# schematic.net
KiCad netlist of a schematic drawn in EAGLE
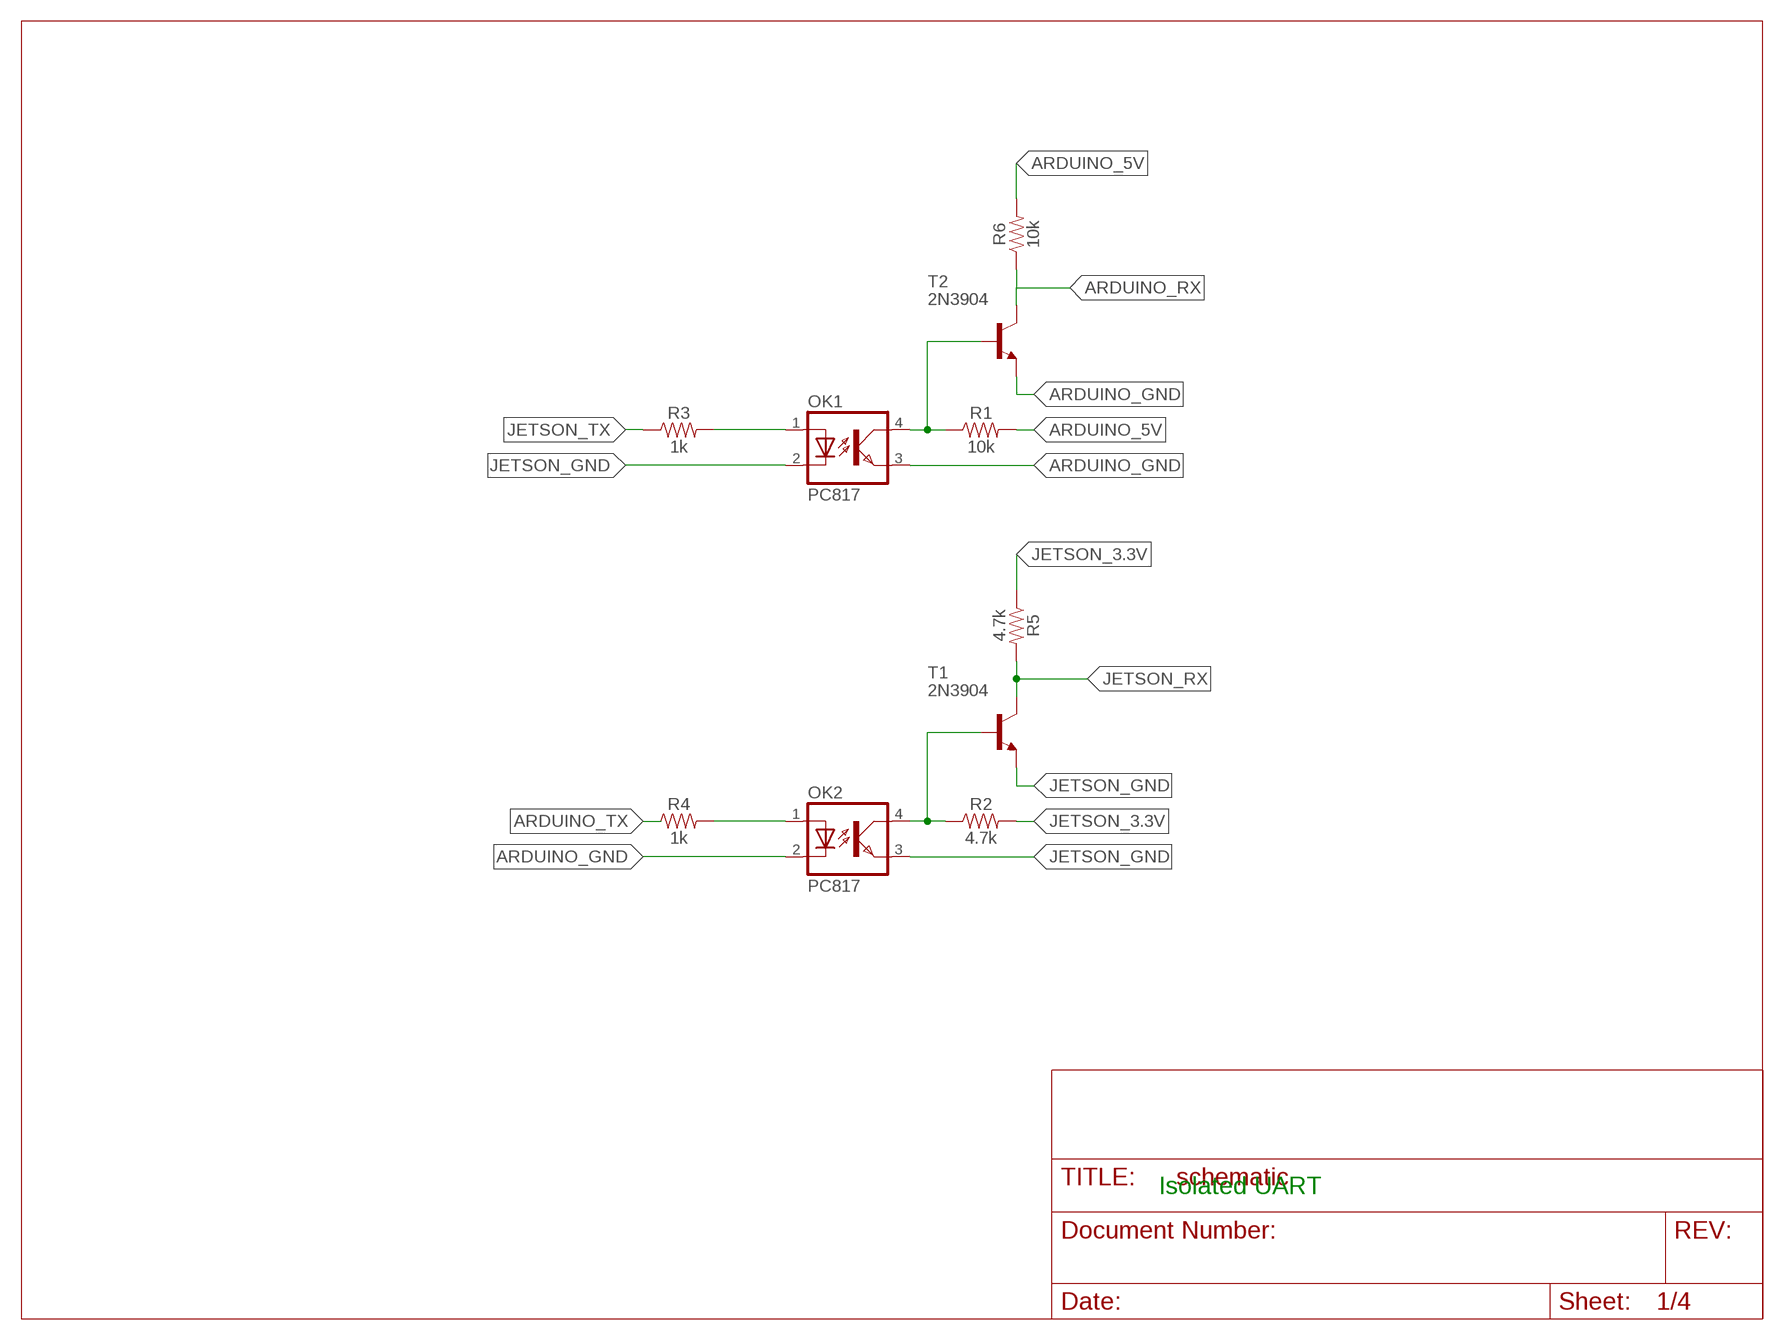
[diagram p0: schematic, sheet 1]
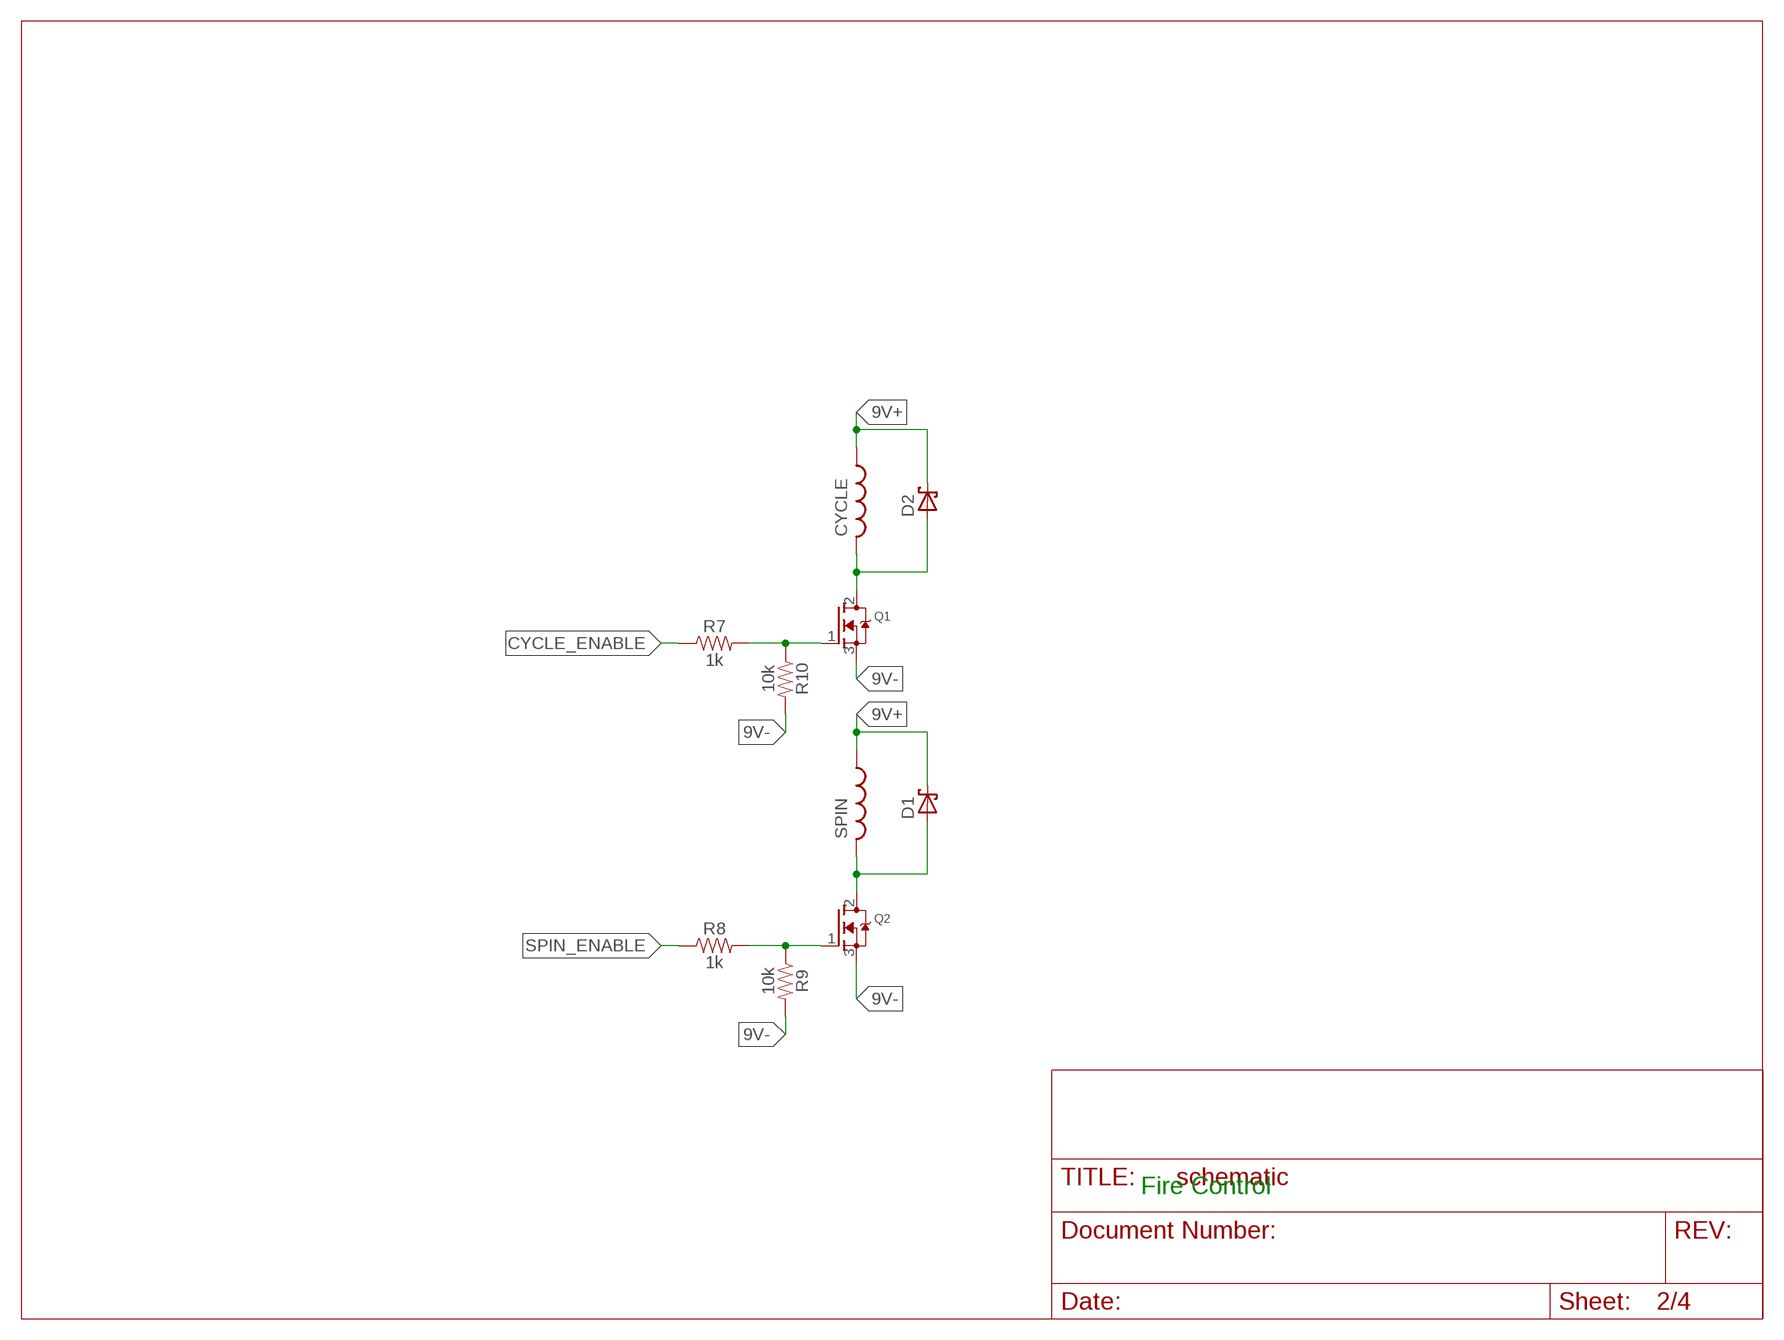
[diagram p1: schematic, sheet 2]
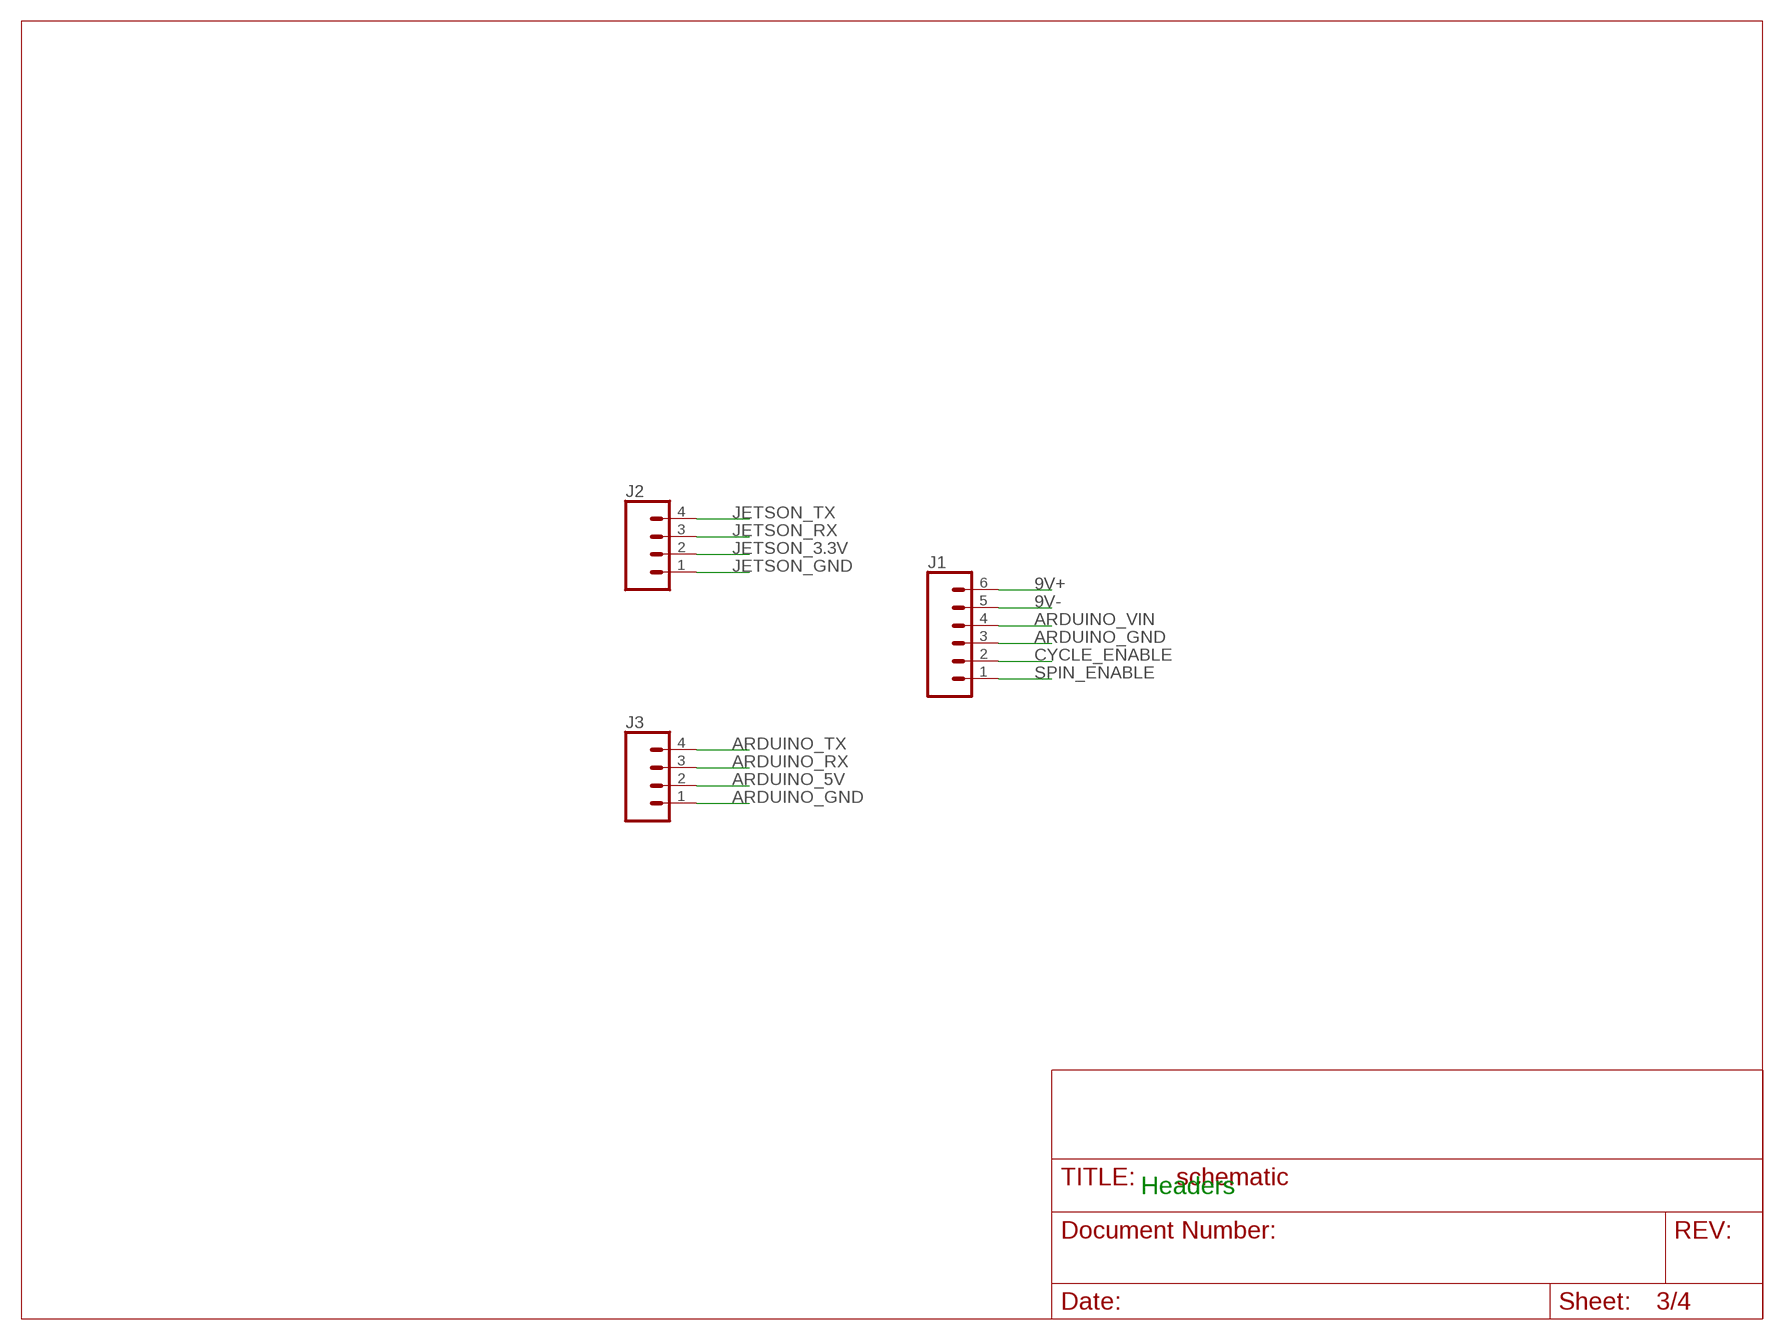
[diagram p2: schematic, sheet 3]
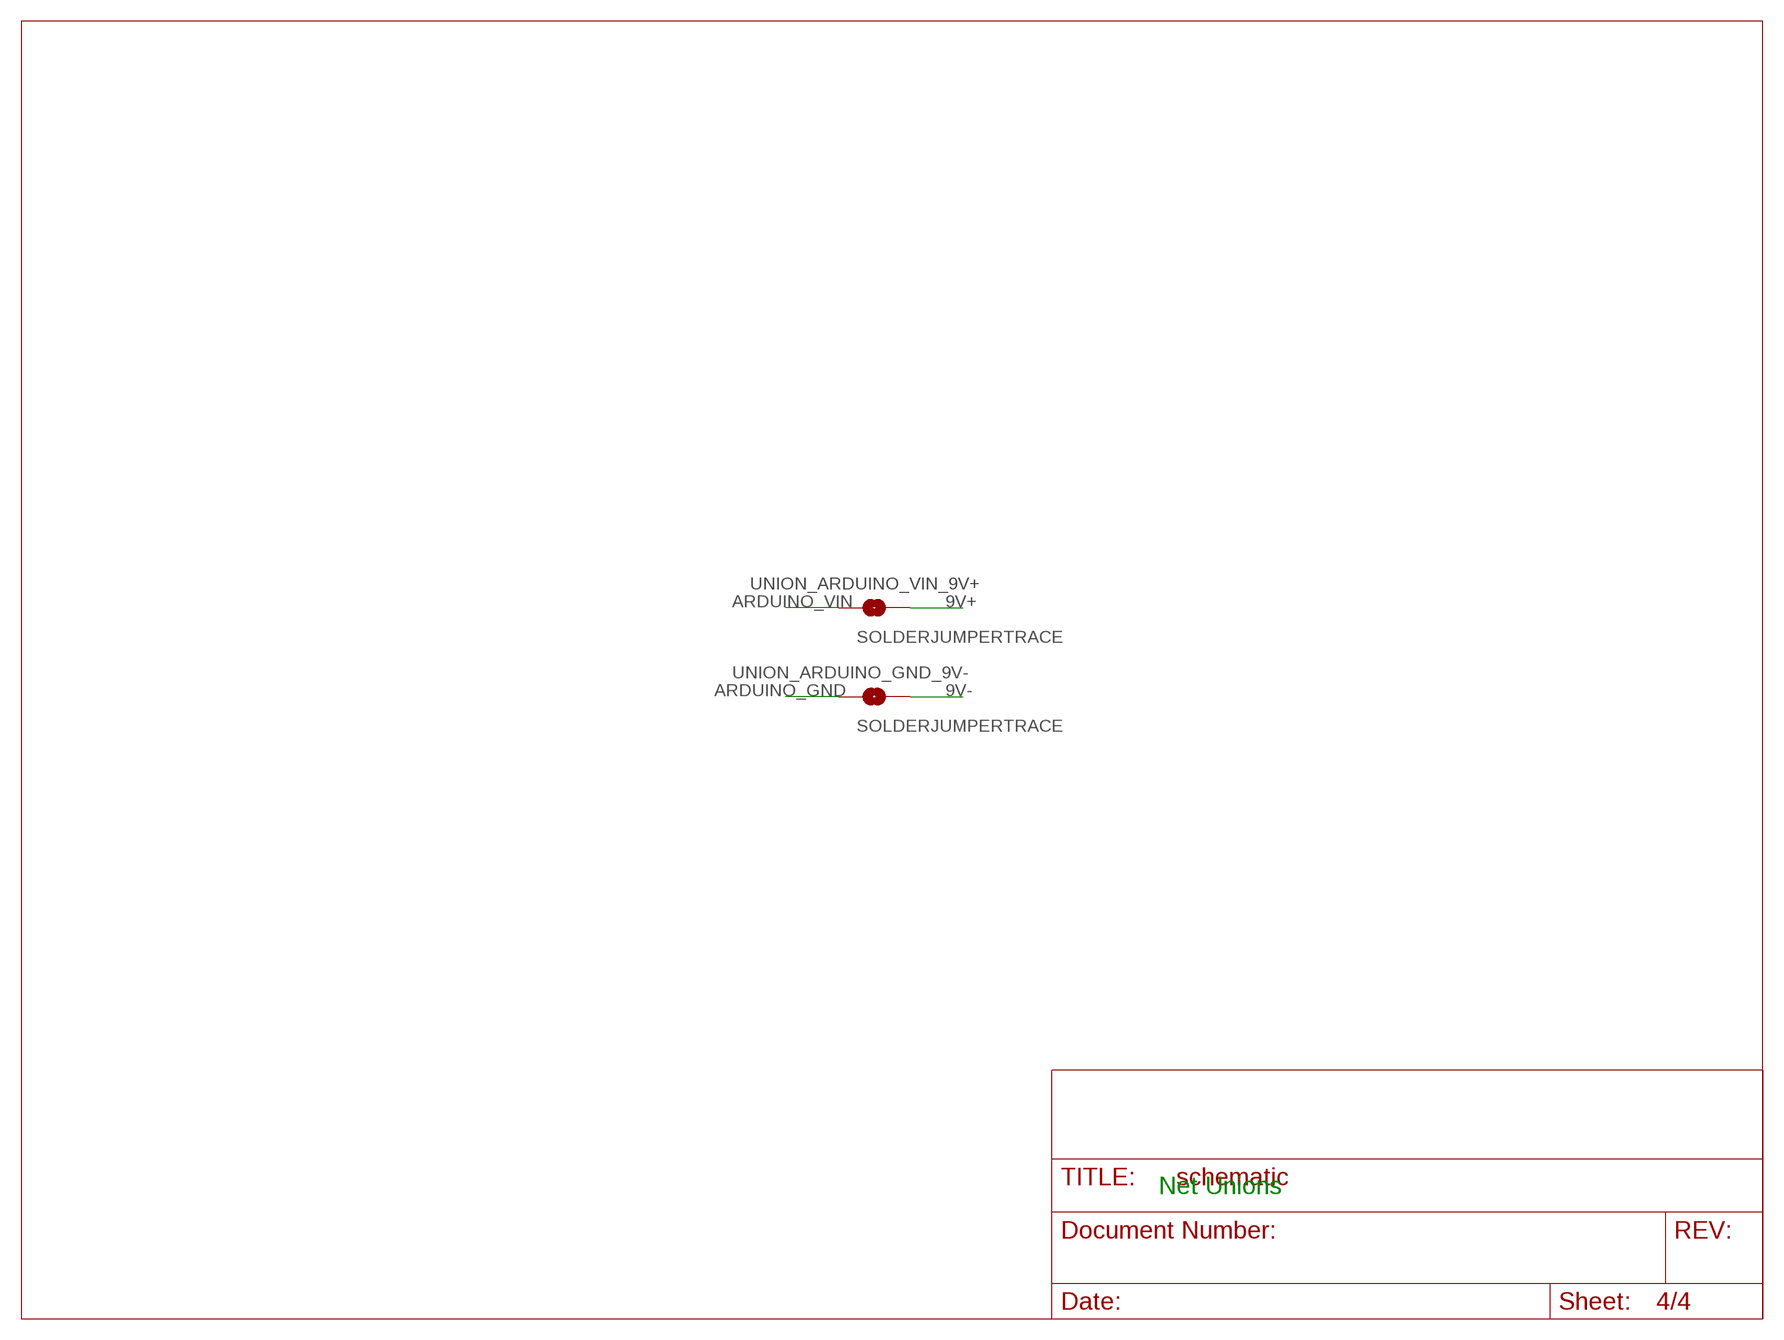
[diagram p3: schematic, sheet 4]

(export (version "E")
  (design (tool "Eeschema 10.0.6"))
  (components
    (comp (ref "CYCLE")
      (value "L-US0204/5")
      (footprint "eagle-import:0204_5")
      (libsource (lib "eagle-import") (part "L-US0204/5"))
    )
    (comp (ref "D1")
      (value "SCHOTTKY-DIODECB417-15")
      (footprint "eagle-import:CB417-15")
      (libsource (lib "eagle-import") (part "SCHOTTKY-DIODECB417-15"))
    )
    (comp (ref "D2")
      (value "SCHOTTKY-DIODECB417-15")
      (footprint "eagle-import:CB417-15")
      (libsource (lib "eagle-import") (part "SCHOTTKY-DIODECB417-15"))
    )
    (comp (ref "Q1")
      (value "MOSFET-NGDS_TO220V")
      (footprint "eagle-import:TO220V")
      (libsource (lib "eagle-import") (part "MOSFET-NGDS_TO220V"))
    )
    (comp (ref "Q2")
      (value "MOSFET-NGDS_TO220V")
      (footprint "eagle-import:TO220V")
      (libsource (lib "eagle-import") (part "MOSFET-NGDS_TO220V"))
    )
    (comp (ref "R7")
      (value "1k")
      (footprint "eagle-import:AXIAL-0.3")
      (libsource (lib "eagle-import") (part "SparkFun-Resistors_532_1KOHM-HORIZ-1/4W-5%"))
    )
    (comp (ref "R8")
      (value "1k")
      (footprint "eagle-import:AXIAL-0.3")
      (libsource (lib "eagle-import") (part "SparkFun-Resistors_532_1KOHM-HORIZ-1/4W-5%"))
    )
    (comp (ref "R9")
      (value "10k")
      (footprint "eagle-import:AXIAL-0.3")
      (libsource (lib "eagle-import") (part "SparkFun-Resistors_532_1KOHM-HORIZ-1/4W-5%"))
    )
    (comp (ref "R10")
      (value "10k")
      (footprint "eagle-import:AXIAL-0.3")
      (libsource (lib "eagle-import") (part "SparkFun-Resistors_532_1KOHM-HORIZ-1/4W-5%"))
    )
    (comp (ref "SPIN")
      (value "L-US0204/5")
      (footprint "eagle-import:0204_5")
      (libsource (lib "eagle-import") (part "L-US0204/5"))
    )
    (comp (ref "J1")
      (value "CONN_06SILK_FEMALE_PTH")
      (footprint "eagle-import:1X06")
      (libsource (lib "eagle-import") (part "CONN_06SILK_FEMALE_PTH"))
    )
    (comp (ref "J2")
      (value "CONN_04")
      (footprint "eagle-import:1X04")
      (libsource (lib "eagle-import") (part "CONN_04"))
    )
    (comp (ref "J3")
      (value "CONN_04")
      (footprint "eagle-import:1X04")
      (libsource (lib "eagle-import") (part "CONN_04"))
    )
    (comp (ref "UNION_ARDUINO_GND_9V-")
      (value "SOLDERJUMPERTRACE")
      (footprint "eagle-import:SJ_2S-TRACE")
      (libsource (lib "eagle-import") (part "SOLDERJUMPERTRACE"))
    )
    (comp (ref "UNION_ARDUINO_VIN_9V+")
      (value "SOLDERJUMPERTRACE")
      (footprint "eagle-import:SJ_2S-TRACE")
      (libsource (lib "eagle-import") (part "SOLDERJUMPERTRACE"))
    )
    (comp (ref "OK1")
      (value "PC817")
      (footprint "eagle-import:DIL04")
      (fields (field (name "MPN") "PC817X4J000F"))
      (libsource (lib "eagle-import") (part "PC817"))
    )
    (comp (ref "OK2")
      (value "PC817")
      (footprint "eagle-import:DIL04")
      (fields (field (name "MPN") "PC817X4J000F"))
      (libsource (lib "eagle-import") (part "PC817"))
    )
    (comp (ref "R1")
      (value "10k")
      (footprint "eagle-import:AXIAL-0.3")
      (libsource (lib "eagle-import") (part "1KOHM-HORIZ-1/4W-1%"))
    )
    (comp (ref "R2")
      (value "4.7k")
      (footprint "eagle-import:AXIAL-0.3")
      (libsource (lib "eagle-import") (part "1KOHM-HORIZ-1/4W-1%"))
    )
    (comp (ref "R3")
      (value "1k")
      (footprint "eagle-import:AXIAL-0.3")
      (libsource (lib "eagle-import") (part "1KOHM-HORIZ-1/4W-1%"))
    )
    (comp (ref "R4")
      (value "1k")
      (footprint "eagle-import:AXIAL-0.3")
      (libsource (lib "eagle-import") (part "1KOHM-HORIZ-1/4W-1%"))
    )
    (comp (ref "R5")
      (value "4.7k")
      (footprint "eagle-import:AXIAL-0.3")
      (libsource (lib "eagle-import") (part "1KOHM-HORIZ-1/4W-1%"))
    )
    (comp (ref "R6")
      (value "10k")
      (footprint "eagle-import:AXIAL-0.3")
      (libsource (lib "eagle-import") (part "1KOHM-HORIZ-1/4W-1%"))
    )
    (comp (ref "T1")
      (value "2N3904")
      (footprint "eagle-import:TO92")
      (libsource (lib "eagle-import") (part "2N3904"))
    )
    (comp (ref "T2")
      (value "2N3904")
      (footprint "eagle-import:TO92")
      (libsource (lib "eagle-import") (part "2N3904"))
    )
  )
  (nets
    (net (code "1") (name "9V+") (class "Default")
      (node (ref "CYCLE") (pin "1") (pinfunction "1_1") (pintype "passive"))
      (node (ref "D1") (pin "C") (pinfunction "C_C") (pintype "passive"))
      (node (ref "D2") (pin "C") (pinfunction "C_C") (pintype "passive"))
      (node (ref "J1") (pin "6") (pinfunction "6_6") (pintype "passive"))
      (node (ref "SPIN") (pin "1") (pinfunction "1_1") (pintype "passive"))
      (node (ref "UNION_ARDUINO_VIN_9V+") (pin "2") (pinfunction "2_2") (pintype "passive"))
    )
    (net (code "2") (name "9V-") (class "Default")
      (node (ref "CYCLE") (pin "2") (pinfunction "2_2") (pintype "passive"))
      (node (ref "D1") (pin "A") (pinfunction "A_A") (pintype "passive"))
      (node (ref "D2") (pin "A") (pinfunction "A_A") (pintype "passive"))
      (node (ref "J1") (pin "5") (pinfunction "5_5") (pintype "passive"))
      (node (ref "Q1") (pin "2") (pinfunction "D_2") (pintype "bidirectional"))
      (node (ref "Q1") (pin "3") (pinfunction "S_3") (pintype "bidirectional"))
      (node (ref "Q2") (pin "2") (pinfunction "D_2") (pintype "bidirectional"))
      (node (ref "Q2") (pin "3") (pinfunction "S_3") (pintype "bidirectional"))
      (node (ref "R10") (pin "P$2") (pinfunction "2_P$2") (pintype "passive"))
      (node (ref "R9") (pin "P$2") (pinfunction "2_P$2") (pintype "passive"))
      (node (ref "SPIN") (pin "2") (pinfunction "2_2") (pintype "passive"))
      (node (ref "UNION_ARDUINO_GND_9V-") (pin "2") (pinfunction "2_2") (pintype "passive"))
    )
    (net (code "3") (name "ARDUINO_5V") (class "Default")
      (node (ref "J3") (pin "2") (pinfunction "2_2") (pintype "passive"))
      (node (ref "R1") (pin "P$2") (pinfunction "2_P$2") (pintype "passive"))
      (node (ref "R6") (pin "P$2") (pinfunction "2_P$2") (pintype "passive"))
    )
    (net (code "4") (name "ARDUINO_GND") (class "Default")
      (node (ref "J1") (pin "3") (pinfunction "3_3") (pintype "passive"))
      (node (ref "J3") (pin "1") (pinfunction "1_1") (pintype "passive"))
      (node (ref "OK1") (pin "3") (pinfunction "EMIT_3") (pintype "passive"))
      (node (ref "OK2") (pin "2") (pinfunction "C_2") (pintype "passive"))
      (node (ref "T2") (pin "3") (pinfunction "E_3") (pintype "passive"))
      (node (ref "UNION_ARDUINO_GND_9V-") (pin "1") (pinfunction "1_1") (pintype "passive"))
    )
    (net (code "5") (name "ARDUINO_RX") (class "Default")
      (node (ref "J3") (pin "3") (pinfunction "3_3") (pintype "passive"))
      (node (ref "R6") (pin "P$1") (pinfunction "1_P$1") (pintype "passive"))
      (node (ref "T2") (pin "1") (pinfunction "C_1") (pintype "passive"))
    )
    (net (code "6") (name "ARDUINO_TX") (class "Default")
      (node (ref "J3") (pin "4") (pinfunction "4_4") (pintype "passive"))
      (node (ref "R4") (pin "P$1") (pinfunction "1_P$1") (pintype "passive"))
    )
    (net (code "7") (name "ARDUINO_VIN") (class "Default")
      (node (ref "J1") (pin "4") (pinfunction "4_4") (pintype "passive"))
      (node (ref "UNION_ARDUINO_VIN_9V+") (pin "1") (pinfunction "1_1") (pintype "passive"))
    )
    (net (code "8") (name "CYCLE_ENABLE") (class "Default")
      (node (ref "J1") (pin "2") (pinfunction "2_2") (pintype "passive"))
      (node (ref "R7") (pin "P$1") (pinfunction "1_P$1") (pintype "passive"))
    )
    (net (code "9") (name "JETSON_3.3V") (class "Default")
      (node (ref "J2") (pin "2") (pinfunction "2_2") (pintype "passive"))
      (node (ref "R2") (pin "P$2") (pinfunction "2_P$2") (pintype "passive"))
      (node (ref "R5") (pin "P$1") (pinfunction "1_P$1") (pintype "passive"))
    )
    (net (code "10") (name "JETSON_GND") (class "Default")
      (node (ref "J2") (pin "1") (pinfunction "1_1") (pintype "passive"))
      (node (ref "OK1") (pin "2") (pinfunction "C_2") (pintype "passive"))
      (node (ref "OK2") (pin "3") (pinfunction "EMIT_3") (pintype "passive"))
      (node (ref "T1") (pin "3") (pinfunction "E_3") (pintype "passive"))
    )
    (net (code "11") (name "JETSON_RX") (class "Default")
      (node (ref "J2") (pin "3") (pinfunction "3_3") (pintype "passive"))
      (node (ref "R5") (pin "P$2") (pinfunction "2_P$2") (pintype "passive"))
      (node (ref "T1") (pin "1") (pinfunction "C_1") (pintype "passive"))
    )
    (net (code "12") (name "JETSON_TX") (class "Default")
      (node (ref "J2") (pin "4") (pinfunction "4_4") (pintype "passive"))
      (node (ref "R3") (pin "P$1") (pinfunction "1_P$1") (pintype "passive"))
    )
    (net (code "13") (name "Net-(OK1-A)") (class "Default")
      (node (ref "OK1") (pin "1") (pinfunction "A_1") (pintype "passive"))
      (node (ref "R3") (pin "P$2") (pinfunction "2_P$2") (pintype "passive"))
    )
    (net (code "14") (name "Net-(OK1-COL)") (class "Default")
      (node (ref "OK1") (pin "4") (pinfunction "COL_4") (pintype "passive"))
      (node (ref "R1") (pin "P$1") (pinfunction "1_P$1") (pintype "passive"))
      (node (ref "T2") (pin "2") (pinfunction "B_2") (pintype "passive"))
    )
    (net (code "15") (name "Net-(OK2-A)") (class "Default")
      (node (ref "OK2") (pin "1") (pinfunction "A_1") (pintype "passive"))
      (node (ref "R4") (pin "P$2") (pinfunction "2_P$2") (pintype "passive"))
    )
    (net (code "16") (name "Net-(OK2-COL)") (class "Default")
      (node (ref "OK2") (pin "4") (pinfunction "COL_4") (pintype "passive"))
      (node (ref "R2") (pin "P$1") (pinfunction "1_P$1") (pintype "passive"))
      (node (ref "T1") (pin "2") (pinfunction "B_2") (pintype "passive"))
    )
    (net (code "17") (name "Net-(Q1-G)") (class "Default")
      (node (ref "Q1") (pin "1") (pinfunction "G_1") (pintype "bidirectional"))
      (node (ref "R10") (pin "P$1") (pinfunction "1_P$1") (pintype "passive"))
      (node (ref "R7") (pin "P$2") (pinfunction "2_P$2") (pintype "passive"))
    )
    (net (code "18") (name "SPIN_ENABLE") (class "Default")
      (node (ref "J1") (pin "1") (pinfunction "1_1") (pintype "passive"))
      (node (ref "Q2") (pin "1") (pinfunction "G_1") (pintype "bidirectional"))
      (node (ref "R8") (pin "P$1") (pinfunction "1_P$1") (pintype "passive"))
      (node (ref "R8") (pin "P$2") (pinfunction "2_P$2") (pintype "passive"))
      (node (ref "R9") (pin "P$1") (pinfunction "1_P$1") (pintype "passive"))
    )
  )
)
